# ESC_Header.net
KiCad netlist of a schematic drawn in Altium Designer
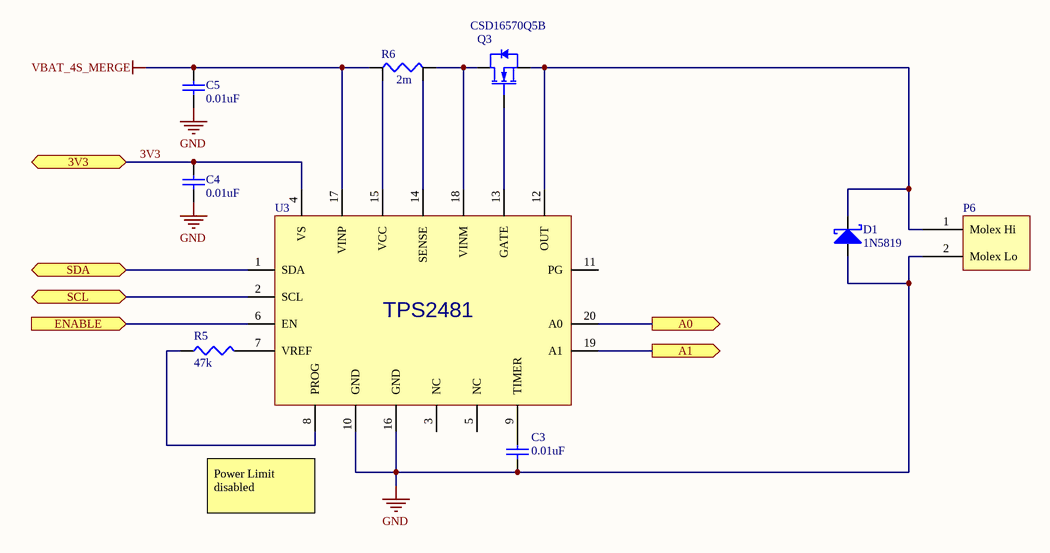
[diagram p0: ESC_Header.SchDoc]

(export (version "E")
  (design (tool "Eeschema 10.0.6"))
  (components
    (comp (ref "C3")
      (value "0.01uF")
      (footprint "C1206")
      (description "Capacitor (Semiconductor SIM Model)")
      (fields (field (name "Comment") "Cap Semi") (field (name "PUBLISHER") "Altium Limited"))
      (libsource (lib "Miscellaneous Devices") (part "Cap Semi"))
    )
    (comp (ref "C4")
      (value "0.01uF")
      (footprint "C1206")
      (description "Capacitor (Semiconductor SIM Model)")
      (fields (field (name "Comment") "Cap Semi") (field (name "PUBLISHER") "Altium Limited"))
      (libsource (lib "Miscellaneous Devices") (part "Cap Semi"))
    )
    (comp (ref "C5")
      (value "0.01uF")
      (footprint "C1206")
      (description "Capacitor (Semiconductor SIM Model)")
      (fields (field (name "Comment") "Cap Semi") (field (name "PUBLISHER") "Altium Limited"))
      (libsource (lib "Miscellaneous Devices") (part "Cap Semi"))
    )
    (comp (ref "D1")
      (value "1N5819")
      (footprint "1N58xx")
      (description "1A Schottky Barrier Rectifier Diode")
      (libsource (lib "Merge_ESC_Board_Library") (part "1N58xx"))
    )
    (comp (ref "P6")
      (value "Motor ?")
      (footprint "76829-0102")
      (fields (field (name "MFGR_PART_NUM") "76829-0102"))
      (libsource (lib "Merge_ESC_Board_Library") (part "Megafit Slim Vert 2 Peg"))
    )
    (comp (ref "Q3")
      (value "CSD16570Q5B")
      (footprint "CSD16570Q5B")
      (description "MOSFET N-CH 25V 100A 8VSON")
      (fields (field (name "MANUFACTURER") "Texas Instruments"))
      (libsource (lib "Merge_ESC_Board_Library") (part "CSD16570Q5B"))
    )
    (comp (ref "R5")
      (value "47k")
      (footprint "J1-0603")
      (description "Resistor")
      (fields (field (name "PUBLISHER") "Altium Limited"))
      (libsource (lib "Miscellaneous Devices") (part "Res3"))
    )
    (comp (ref "R6")
      (value "2m")
      (footprint "WSL27262L000FEB")
      (libsource (lib "Merge_ESC_Board_Library") (part "WSL27262L000FEB"))
    )
    (comp (ref "U3")
      (value "TPS2481")
      (footprint "TPS2481")
      (description "Positive voltage, intelligent protection device/hotswap controller and I2C current monitor")
      (libsource (lib "Merge_ESC_Board_Library") (part "TPS2481"))
    )
  )
  (nets
    (net (code "1") (name "/3V3") (class "Default")
      (node (ref "C4") (pin "2") (pinfunction "2_2") (pintype "passive"))
      (node (ref "U3") (pin "4") (pinfunction "VS_4") (pintype "passive"))
    )
    (net (code "2") (name "/A0") (class "Default")
      (node (ref "U3") (pin "20") (pinfunction "A0_20") (pintype "passive"))
    )
    (net (code "3") (name "/A1") (class "Default")
      (node (ref "U3") (pin "19") (pinfunction "A1_19") (pintype "passive"))
    )
    (net (code "4") (name "/ENABLE") (class "Default")
      (node (ref "U3") (pin "6") (pinfunction "EN_6") (pintype "passive"))
    )
    (net (code "5") (name "/SCL") (class "Default")
      (node (ref "U3") (pin "2") (pinfunction "SCL_2") (pintype "passive"))
    )
    (net (code "6") (name "/SDA") (class "Default")
      (node (ref "U3") (pin "1") (pinfunction "SDA_1") (pintype "passive"))
    )
    (net (code "7") (name "GND") (class "Default")
      (node (ref "C3") (pin "1") (pinfunction "1_1") (pintype "passive"))
      (node (ref "C4") (pin "1") (pinfunction "1_1") (pintype "passive"))
      (node (ref "C5") (pin "1") (pinfunction "1_1") (pintype "passive"))
      (node (ref "D1") (pin "A") (pinfunction "Anode_A") (pintype "passive"))
      (node (ref "P6") (pin "2") (pinfunction "Molex_Lo_2") (pintype "passive"))
      (node (ref "U3") (pin "10") (pinfunction "GND_10") (pintype "passive"))
      (node (ref "U3") (pin "16") (pinfunction "GND_16") (pintype "passive"))
    )
    (net (code "8") (name "Net-(D1-Cathode)") (class "Default")
      (node (ref "D1") (pin "K") (pinfunction "Cathode_K") (pintype "passive"))
      (node (ref "P6") (pin "1") (pinfunction "Molex_Hi_1") (pintype "passive"))
      (node (ref "Q3") (pin "S") (pinfunction "Source_S") (pintype "passive"))
      (node (ref "U3") (pin "12") (pinfunction "OUT_12") (pintype "passive"))
    )
    (net (code "9") (name "Net-(Q3-Drain)") (class "Default")
      (node (ref "Q3") (pin "D") (pinfunction "Drain_D") (pintype "passive"))
      (node (ref "R6") (pin "2") (pinfunction "1_2") (pintype "passive"))
      (node (ref "U3") (pin "18") (pinfunction "VINM_18") (pintype "passive"))
    )
    (net (code "10") (name "Net-(Q3-Gate)") (class "Default")
      (node (ref "Q3") (pin "G") (pinfunction "Gate_G") (pintype "passive"))
      (node (ref "U3") (pin "13") (pinfunction "GATE_13") (pintype "passive"))
    )
    (net (code "11") (name "Net-(R6-3)") (class "Default")
      (node (ref "R6") (pin "4") (pinfunction "3_4") (pintype "passive"))
      (node (ref "U3") (pin "14") (pinfunction "SENSE_14") (pintype "passive"))
    )
    (net (code "12") (name "Net-(R6-4)") (class "Default")
      (node (ref "R6") (pin "3") (pinfunction "4_3") (pintype "passive"))
      (node (ref "U3") (pin "15") (pinfunction "VCC_15") (pintype "passive"))
    )
    (net (code "13") (name "Net-(U3-PROG)") (class "Default")
      (node (ref "R5") (pin "1") (pinfunction "1_1") (pintype "passive"))
      (node (ref "U3") (pin "8") (pinfunction "PROG_8") (pintype "passive"))
    )
    (net (code "14") (name "Net-(U3-TIMER)") (class "Default")
      (node (ref "C3") (pin "2") (pinfunction "2_2") (pintype "passive"))
      (node (ref "U3") (pin "9") (pinfunction "TIMER_9") (pintype "passive"))
    )
    (net (code "15") (name "Net-(U3-VREF)") (class "Default")
      (node (ref "R5") (pin "2") (pinfunction "2_2") (pintype "passive"))
      (node (ref "U3") (pin "7") (pinfunction "VREF_7") (pintype "passive"))
    )
    (net (code "16") (name "VBAT_4S_MERGE") (class "Default")
      (node (ref "C5") (pin "2") (pinfunction "2_2") (pintype "passive"))
      (node (ref "R6") (pin "1") (pinfunction "2_1") (pintype "passive"))
      (node (ref "U3") (pin "17") (pinfunction "VINP_17") (pintype "passive"))
    )
    (net (code "17") (name "unconnected-(U3-NC-Pad3)") (class "Default")
      (node (ref "U3") (pin "3") (pinfunction "NC_3") (pintype "passive"))
    )
    (net (code "18") (name "unconnected-(U3-NC-Pad5)") (class "Default")
      (node (ref "U3") (pin "5") (pinfunction "NC_5") (pintype "passive"))
    )
    (net (code "19") (name "unconnected-(U3-PG-Pad11)") (class "Default")
      (node (ref "U3") (pin "11") (pinfunction "PG_11") (pintype "passive"))
    )
  )
)
